# CAN.net
KiCad netlist of a schematic drawn in Altium Designer
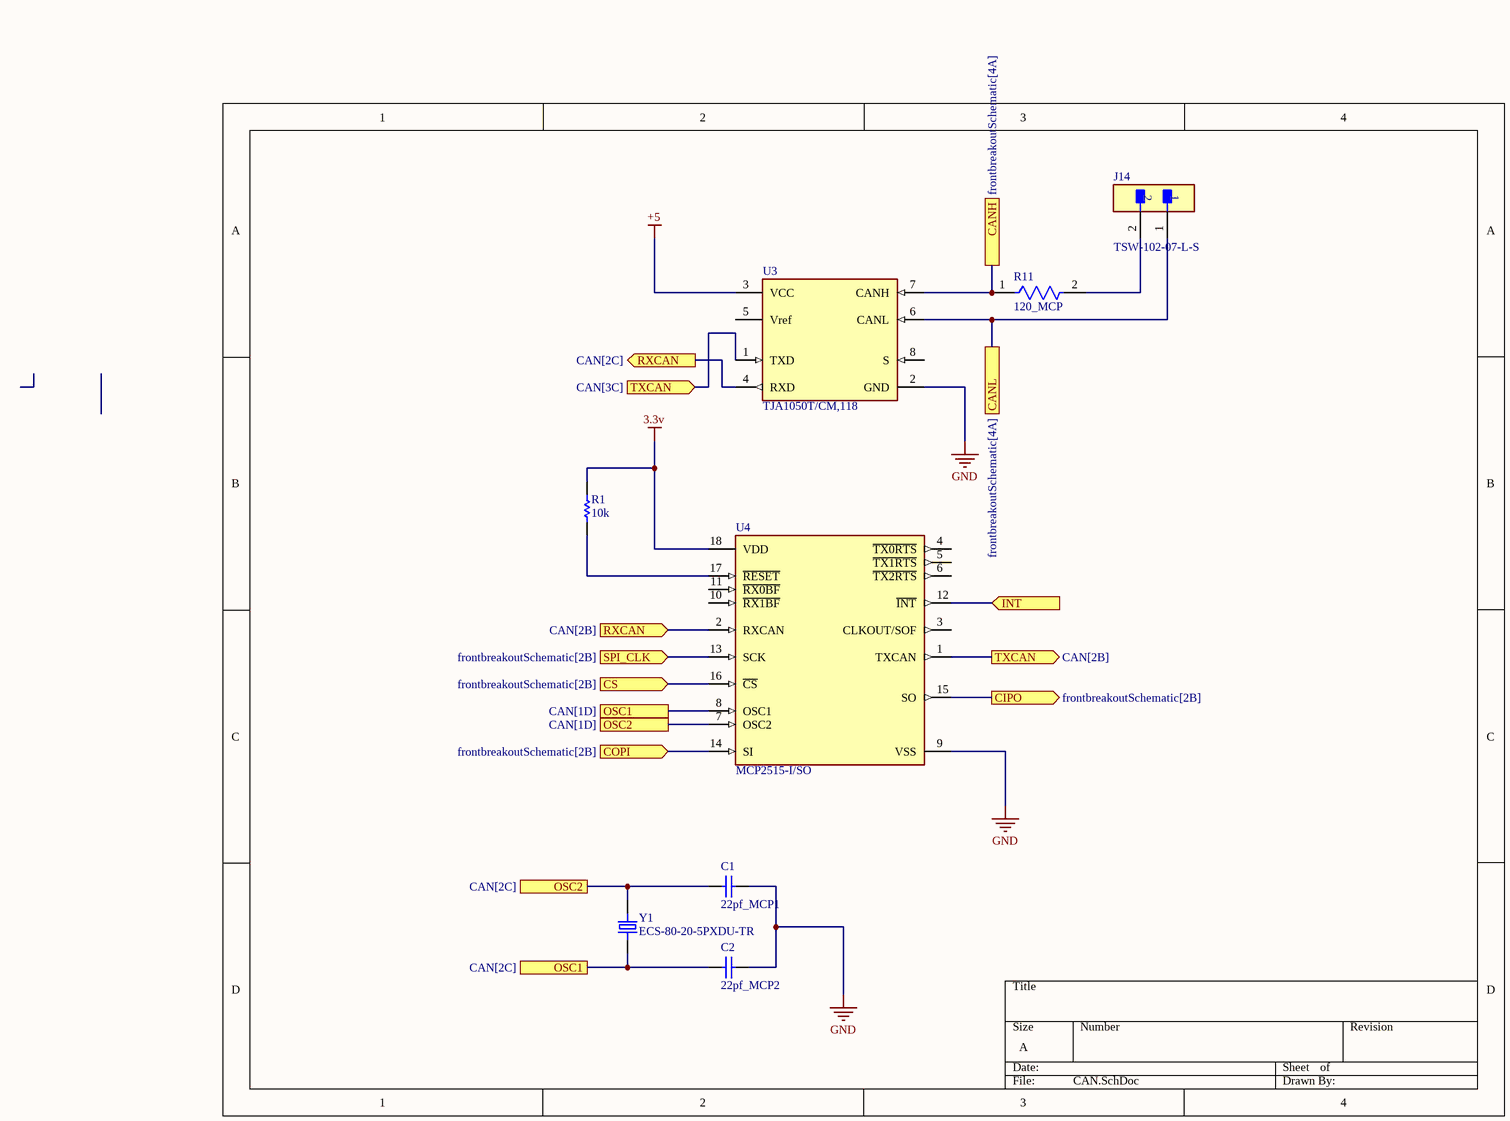
[diagram p0: CAN.SchDoc]

(export (version "E")
  (design (tool "Eeschema 10.0.6"))
  (components
    (comp (ref "C1")
      (value "22pf_MCP1")
      (footprint "CAPC2013X145X50NL20T20")
      (fields (field (name "MANUFACTURER") "Vitramon") (field (name "PART NUMBER") "VJ0805A220GXXCW1BC"))
      (libsource (lib "Altium Content Vault") (part "CAP"))
    )
    (comp (ref "C2")
      (value "22pf_MCP2")
      (footprint "CAPC2013X145X50NL20T20")
      (fields (field (name "MANUFACTURER") "Vitramon") (field (name "PART NUMBER") "VJ0805A220GXXCW1BC"))
      (libsource (lib "Altium Content Vault") (part "CAP"))
    )
    (comp (ref "J14")
      (value "TSW-102-07-L-S")
      (footprint "FP-TSW-102-07-L-S-MFG")
      (description "CONN HEADER VERT 2POS 2.54MM")
      (libsource (lib "Altium Content Vault") (part "3bc925449376181038e59eaffc5286c"))
    )
    (comp (ref "R1")
      (value "10k")
      (footprint "RESC3116X65X50NL20T20")
      (description "CRCW120610K0FKEAHP")
      (fields (field (name "MANUFACTURER") "Vishay Dale"))
      (libsource (lib "Altium Content Vault") (part "RES"))
    )
    (comp (ref "R11")
      (value "120_MCP")
      (footprint "FP-CRCW0805-e3-IPC_C")
      (description "RES Thick Film, 4.02Ω, 1%, 0.125W, 200ppm/°C, 0805")
      (fields (field (name "TOLERANCE") "1%"))
      (libsource (lib "Altium Content Vault") (part "1029c3af85768c4190bb7ad29bc67b5"))
    )
    (comp (ref "U3")
      (value "TJA1050T/CM,118")
      (footprint "FP-SOT96-1-IPC_A")
      (description "IC TRANSCEIVER HALF 1/1 8SO")
      (libsource (lib "Altium Content Vault") (part "cfdefafd38a55dc0607790f57b8a78f"))
    )
    (comp (ref "U4")
      (value "MCP2515-I/SO")
      (footprint "FP-C04-051-MFG")
      (description "IC CAN CONTROLLER W/SPI 18SOIC")
      (fields
        (field (name "MANUFACTURER") "Microchip")
        (field (name "OCTOPART") "https://octopart.com/mcp2515-i%2Fso-microchip-430187")
      )
      (libsource (lib "Altium Content Vault") (part "1c78ea6ff576bac94664e2637e1b479"))
    )
    (comp (ref "Y1")
      (value "ECS-80-20-5PXDU-TR")
      (footprint "XTAL_ECS-80-20-5PXDU-TR")
      (description "8MHz Â±30ppm Crystal 20pF 60 Ohms HC-49/US")
      (fields (field (name "MF") "ECS Inc."))
      (libsource (lib "ECS-80-20-5PXDU-TR") (part "ECS-80-20-5PXDU-TR"))
    )
  )
  (nets
    (net (code "1") (name "+5") (class "Default")
      (node (ref "U3") (pin "3") (pinfunction "VCC_3") (pintype "power_in"))
    )
    (net (code "2") (name "/CANH") (class "Default")
      (node (ref "R11") (pin "1") (pinfunction "1_1") (pintype "passive"))
      (node (ref "U3") (pin "7") (pinfunction "CANH_7") (pintype "input"))
    )
    (net (code "3") (name "/CANL") (class "Default")
      (node (ref "J14") (pin "1") (pinfunction "1_1") (pintype "passive"))
      (node (ref "U3") (pin "6") (pinfunction "CANL_6") (pintype "input"))
    )
    (net (code "4") (name "/CIPO") (class "Default")
      (node (ref "U4") (pin "15") (pinfunction "SO_15") (pintype "output"))
    )
    (net (code "5") (name "/COPI") (class "Default")
      (node (ref "U4") (pin "14") (pinfunction "SI_14") (pintype "input"))
    )
    (net (code "6") (name "/CS") (class "Default")
      (node (ref "U4") (pin "16") (pinfunction "~{CS}_16") (pintype "input"))
    )
    (net (code "7") (name "/INT") (class "Default")
      (node (ref "U4") (pin "12") (pinfunction "~{INT}_12") (pintype "output"))
    )
    (net (code "8") (name "/OSC1") (class "Default")
      (node (ref "C2") (pin "1") (pinfunction "1_1") (pintype "passive"))
      (node (ref "U4") (pin "8") (pinfunction "OSC1_8") (pintype "input"))
      (node (ref "Y1") (pin "1") (pinfunction "1_1") (pintype "passive"))
    )
    (net (code "9") (name "/OSC2") (class "Default")
      (node (ref "C1") (pin "1") (pinfunction "1_1") (pintype "passive"))
      (node (ref "U4") (pin "7") (pinfunction "OSC2_7") (pintype "input"))
      (node (ref "Y1") (pin "2") (pinfunction "2_2") (pintype "passive"))
    )
    (net (code "10") (name "/RXCAN") (class "Default")
      (node (ref "U3") (pin "4") (pinfunction "RXD_4") (pintype "output"))
      (node (ref "U4") (pin "2") (pinfunction "RXCAN_2") (pintype "input"))
    )
    (net (code "11") (name "/SPI_CLK") (class "Default")
      (node (ref "U4") (pin "13") (pinfunction "SCK_13") (pintype "input"))
    )
    (net (code "12") (name "/TXCAN") (class "Default")
      (node (ref "U3") (pin "1") (pinfunction "TXD_1") (pintype "input"))
      (node (ref "U4") (pin "1") (pinfunction "TXCAN_1") (pintype "output"))
    )
    (net (code "13") (name "3.3v") (class "Default")
      (node (ref "R1") (pin "2") (pinfunction "2_2") (pintype "passive"))
      (node (ref "U4") (pin "18") (pinfunction "VDD_18") (pintype "power_in"))
    )
    (net (code "14") (name "GND") (class "Default")
      (node (ref "C1") (pin "2") (pinfunction "2_2") (pintype "passive"))
      (node (ref "C2") (pin "2") (pinfunction "2_2") (pintype "passive"))
      (node (ref "U3") (pin "2") (pinfunction "GND_2") (pintype "power_in"))
      (node (ref "U4") (pin "9") (pinfunction "VSS_9") (pintype "power_in"))
    )
    (net (code "15") (name "Net-(J14-Pad2)") (class "Default")
      (node (ref "J14") (pin "2") (pinfunction "2_2") (pintype "passive"))
      (node (ref "R11") (pin "2") (pinfunction "2_2") (pintype "passive"))
    )
    (net (code "16") (name "Net-(U4-~{RESET})") (class "Default")
      (node (ref "R1") (pin "1") (pinfunction "1_1") (pintype "passive"))
      (node (ref "U4") (pin "17") (pinfunction "~{RESET}_17") (pintype "input"))
    )
    (net (code "17") (name "unconnected-(U3-S-Pad8)") (class "Default")
      (node (ref "U3") (pin "8") (pinfunction "S_8") (pintype "input"))
    )
    (net (code "18") (name "unconnected-(U3-Vref-Pad5)") (class "Default")
      (node (ref "U3") (pin "5") (pinfunction "Vref_5") (pintype "power_in"))
    )
    (net (code "19") (name "unconnected-(U4-CLKOUT{slash}SOF-Pad3)") (class "Default")
      (node (ref "U4") (pin "3") (pinfunction "CLKOUT/SOF_3") (pintype "output"))
    )
    (net (code "20") (name "unconnected-(U4-~{RX0BF}-Pad11)") (class "Default")
      (node (ref "U4") (pin "11") (pinfunction "~{RX0BF}_11") (pintype "input"))
    )
    (net (code "21") (name "unconnected-(U4-~{RX1BF}-Pad10)") (class "Default")
      (node (ref "U4") (pin "10") (pinfunction "~{RX1BF}_10") (pintype "input"))
    )
    (net (code "22") (name "unconnected-(U4-~{TX0RTS}-Pad4)") (class "Default")
      (node (ref "U4") (pin "4") (pinfunction "~{TX0RTS}_4") (pintype "output"))
    )
    (net (code "23") (name "unconnected-(U4-~{TX1RTS}-Pad5)") (class "Default")
      (node (ref "U4") (pin "5") (pinfunction "~{TX1RTS}_5") (pintype "output"))
    )
    (net (code "24") (name "unconnected-(U4-~{TX2RTS}-Pad6)") (class "Default")
      (node (ref "U4") (pin "6") (pinfunction "~{TX2RTS}_6") (pintype "output"))
    )
  )
)
